# CL_meter.net
KiCad netlist of a schematic drawn in Altium Designer
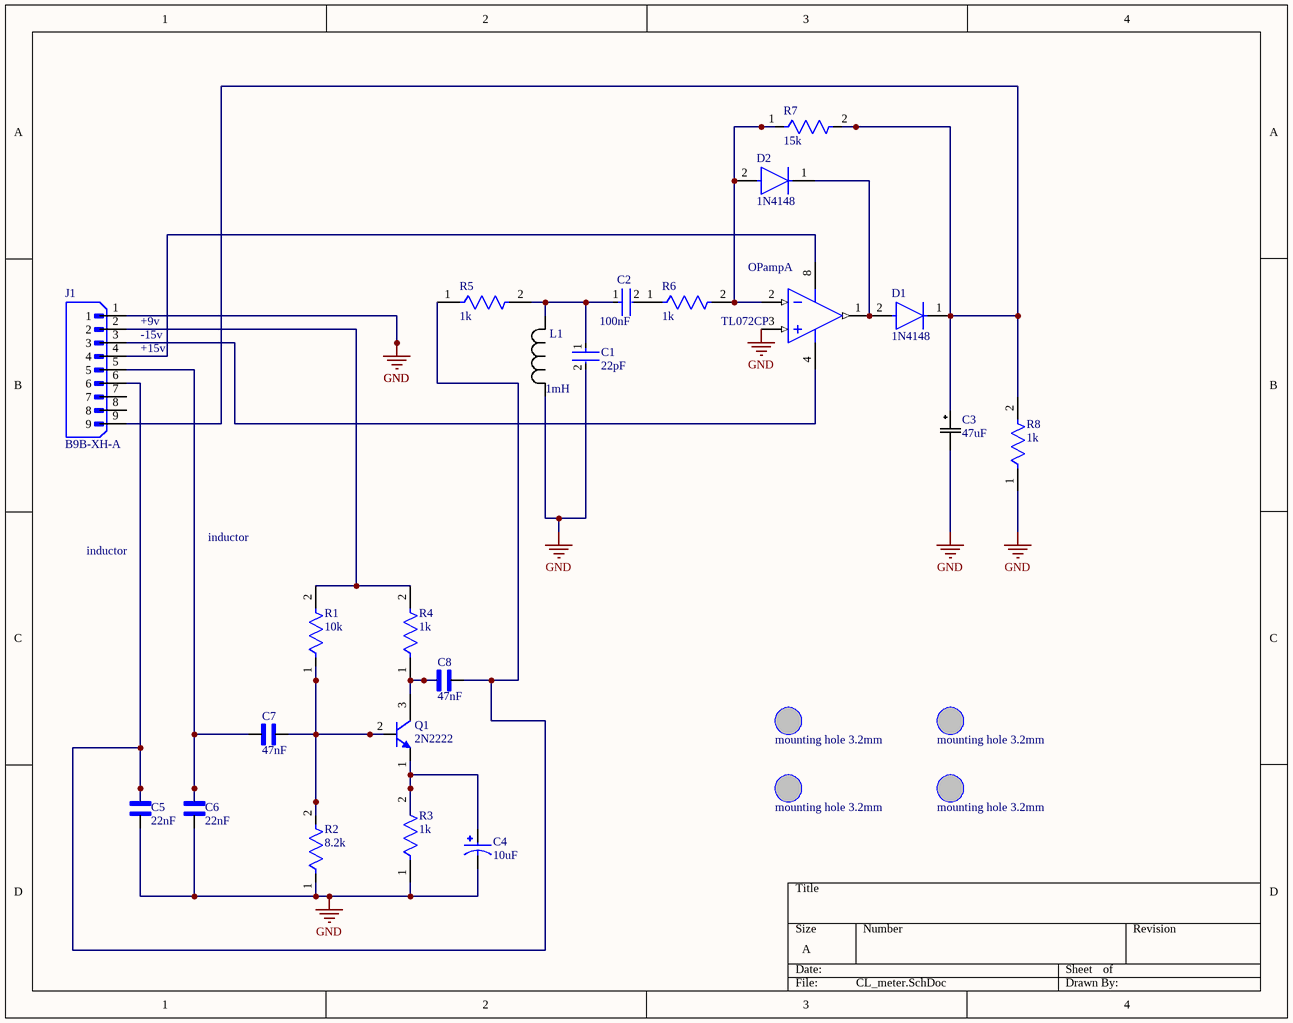
[diagram p0: CL_meter.SchDoc]

(export (version "E")
  (design (tool "Eeschema 10.0.6"))
  (components
    (comp (ref "C1")
      (value "22pF")
      (footprint "FP-DE2_D8_T5_F7_5_d0_6-0-MFG")
      (description "DE21XKY220JN3AM02F Cap Ceramic Disc 22pF 250VAC 5% Thru-Hole Ammo Pack")
      (fields (field (name "TOLERANCE") "5%"))
      (libsource (lib "Altium Content Vault") (part "2f572a3ab75e460155c5317ce189eff"))
    )
    (comp (ref "C2")
      (value "100nF")
      (footprint "FP-K15H5-MFG")
      (description "CAP CER 0.1UF 50V X7R RADIAL")
      (fields (field (name "TOLERANCE") "10%") (field (name "VOLTAGE") "50V"))
      (libsource (lib "Altium Content Vault") (part "02cd4be3c70576c341d710602a673aa"))
    )
    (comp (ref "C3")
      (value "47uF")
      (footprint "3")
      (description "No Description Available")
      (libsource (lib "Schlib1") (part "UVK2A470MPD1TD"))
    )
    (comp (ref "C4")
      (value "10uF")
      (footprint "10uF")
      (description "Cap Aluminum Lytic 10uF 25V 20% (4 X 7mm) Radial 5mm 28mA 1000h 85Â°C Ammo Pack")
      (fields (field (name "MP") "ECEA1EKA100B") (field (name "MF") "Panasonic"))
      (libsource (lib "Schlib1") (part "10uF"))
    )
    (comp (ref "C5")
      (value "22nF")
      (footprint "CAPRR254W54L381T254H466")
      (fields (field (name "MF") "KEMET") (field (name "MP") "C315C223K5R5TA"))
      (libsource (lib "Schlib1") (part "C315C223K5R5TA"))
    )
    (comp (ref "C6")
      (value "22nF")
      (footprint "CAPRR254W54L381T254H466")
      (fields (field (name "MF") "KEMET") (field (name "MP") "C315C223K5R5TA"))
      (libsource (lib "Schlib1") (part "C315C223K5R5TA"))
    )
    (comp (ref "C7")
      (value "47nF")
      (footprint "CAPRR254W54L381T254H466")
      (fields (field (name "MF") "KEMET") (field (name "MP") "C315C473M5U5TA"))
      (libsource (lib "Schlib1") (part "C315C473M5U5TA"))
    )
    (comp (ref "C8")
      (value "47nF")
      (footprint "CAPRR254W54L381T254H466")
      (fields (field (name "MF") "KEMET") (field (name "MP") "C315C473M5U5TA"))
      (libsource (lib "Schlib1") (part "C315C473M5U5TA"))
    )
    (comp (ref "D1")
      (value "1N4148")
      (footprint "FP-017AG-MFG")
      (description "DIODE GEN PURP 100V 200MA DO35")
      (fields (field (name "VOLTAGE") "100V"))
      (libsource (lib "Altium Content Vault") (part "d7152d700b627762746794eb795d46e"))
    )
    (comp (ref "D2")
      (value "1N4148")
      (footprint "FP-017AG-MFG")
      (description "DIODE GEN PURP 100V 200MA DO35")
      (fields (field (name "VOLTAGE") "100V"))
      (libsource (lib "Altium Content Vault") (part "d7152d700b627762746794eb795d46e"))
    )
    (comp (ref "J1")
      (value "B9B-XH-A")
      (footprint "JST_B9B-XH-A")
      (fields (field (name "MF") "{'manufacturer': u'JST Sales America Inc.'}"))
      (libsource (lib "Schlib1") (part "B9B-XH-A"))
    )
    (comp (ref "L1")
      (value "1mH")
      (footprint "IND_BOURNS_RLB9012")
      (description "No Description Available")
      (libsource (lib "Schlib1") (part "RLB9012-102KL"))
    )
    (comp (ref "OPamp")
      (value "TL072CP")
      (footprint "P0008A")
      (fields (field (name "MANUFACTURER") "Texas Instruments"))
      (libsource (lib "Altium Content Vault") (part "TI-AMP-D6-2-8_D"))
    )
    (comp (ref "Q1")
      (value "2N2222")
      (footprint "MLTC-TO-18-3")
      (description "Low Power Bipolar NPN Transistor, 30 V, -65 to 200 degC, 3-Pin TO-18, RoHS, Bulk")
      (fields (field (name "MANUFACTURER") "Multicomp"))
      (libsource (lib "Altium Content Vault") (part "BJT-NPN-EBC-3"))
    )
    (comp (ref "R1")
      (value "10k")
      (footprint "FP-MRS25-MFG")
      (fields (field (name "TOLERANCE") "1%"))
      (libsource (lib "Altium Content Vault") (part "1029c3af85768c4190bb7ad29bc67b5"))
    )
    (comp (ref "R2")
      (value "8.2k")
      (footprint "FP-MRS25-MFG")
      (fields (field (name "TOLERANCE") "1%"))
      (libsource (lib "Altium Content Vault") (part "1029c3af85768c4190bb7ad29bc67b5"))
    )
    (comp (ref "R3")
      (value "1k")
      (footprint "FP-MRS25-MFG")
      (fields (field (name "TOLERANCE") "1%"))
      (libsource (lib "Altium Content Vault") (part "1029c3af85768c4190bb7ad29bc67b5"))
    )
    (comp (ref "R4")
      (value "1k")
      (footprint "FP-MRS25-MFG")
      (fields (field (name "TOLERANCE") "1%"))
      (libsource (lib "Altium Content Vault") (part "1029c3af85768c4190bb7ad29bc67b5"))
    )
    (comp (ref "R5")
      (value "1k")
      (footprint "FP-MRS25-MFG")
      (fields (field (name "TOLERANCE") "1%"))
      (libsource (lib "Altium Content Vault") (part "1029c3af85768c4190bb7ad29bc67b5"))
    )
    (comp (ref "R6")
      (value "1k")
      (footprint "FP-MRS25-MFG")
      (fields (field (name "TOLERANCE") "1%"))
      (libsource (lib "Altium Content Vault") (part "1029c3af85768c4190bb7ad29bc67b5"))
    )
    (comp (ref "R7")
      (value "15k")
      (footprint "FP-MRS25-MFG")
      (fields (field (name "TOLERANCE") "1%"))
      (libsource (lib "Altium Content Vault") (part "1029c3af85768c4190bb7ad29bc67b5"))
    )
    (comp (ref "R8")
      (value "1k")
      (footprint "FP-MRS25-MFG")
      (fields (field (name "TOLERANCE") "1%"))
      (libsource (lib "Altium Content Vault") (part "1029c3af85768c4190bb7ad29bc67b5"))
    )
  )
  (nets
    (net (code "1") (name "GND") (class "Default")
      (node (ref "C1") (pin "2") (pinfunction "2_2") (pintype "passive"))
      (node (ref "C3") (pin "2") (pinfunction "2_2") (pintype "passive"))
      (node (ref "C4") (pin "N") (pinfunction "N_N") (pintype "passive"))
      (node (ref "C5") (pin "1") (pinfunction "1_1") (pintype "passive"))
      (node (ref "C6") (pin "1") (pinfunction "1_1") (pintype "passive"))
      (node (ref "J1") (pin "1") (pinfunction "1_1") (pintype "passive"))
      (node (ref "L1") (pin "2") (pinfunction "2_2") (pintype "passive"))
      (node (ref "OPamp") (pin "3") (pinfunction "IN1+_3") (pintype "input"))
      (node (ref "R2") (pin "1") (pinfunction "1_1") (pintype "passive"))
      (node (ref "R3") (pin "1") (pinfunction "1_1") (pintype "passive"))
      (node (ref "R8") (pin "1") (pinfunction "1_1") (pintype "passive"))
    )
    (net (code "2") (name "Net-(C1-Pad1)") (class "Default")
      (node (ref "C1") (pin "1") (pinfunction "1_1") (pintype "passive"))
      (node (ref "C2") (pin "1") (pinfunction "1_1") (pintype "passive"))
      (node (ref "L1") (pin "1") (pinfunction "1_1") (pintype "passive"))
      (node (ref "R5") (pin "2") (pinfunction "2_2") (pintype "passive"))
    )
    (net (code "3") (name "Net-(C2-Pad2)") (class "Default")
      (node (ref "C2") (pin "2") (pinfunction "2_2") (pintype "passive"))
      (node (ref "R6") (pin "1") (pinfunction "1_1") (pintype "passive"))
    )
    (net (code "4") (name "Net-(C5-Pad2)") (class "Default")
      (node (ref "C5") (pin "2") (pinfunction "2_2") (pintype "passive"))
      (node (ref "C8") (pin "2") (pinfunction "2_2") (pintype "passive"))
      (node (ref "J1") (pin "6") (pinfunction "6_6") (pintype "passive"))
      (node (ref "R5") (pin "1") (pinfunction "1_1") (pintype "passive"))
    )
    (net (code "5") (name "Net-(C6-Pad2)") (class "Default")
      (node (ref "C6") (pin "2") (pinfunction "2_2") (pintype "passive"))
      (node (ref "C7") (pin "1") (pinfunction "1_1") (pintype "passive"))
      (node (ref "J1") (pin "5") (pinfunction "5_5") (pintype "passive"))
    )
    (net (code "6") (name "Net-(D1-A)") (class "Default")
      (node (ref "D1") (pin "2") (pinfunction "A_2") (pintype "passive"))
      (node (ref "D2") (pin "1") (pinfunction "C_1") (pintype "passive"))
      (node (ref "OPamp") (pin "1") (pinfunction "OUT1_1") (pintype "output"))
    )
    (net (code "7") (name "Net-(D1-C)") (class "Default")
      (node (ref "C3") (pin "1") (pinfunction "1_1") (pintype "passive"))
      (node (ref "D1") (pin "1") (pinfunction "C_1") (pintype "passive"))
      (node (ref "J1") (pin "9") (pinfunction "9_9") (pintype "passive"))
      (node (ref "R7") (pin "2") (pinfunction "2_2") (pintype "passive"))
      (node (ref "R8") (pin "2") (pinfunction "2_2") (pintype "passive"))
    )
    (net (code "8") (name "Net-(D2-A)") (class "Default")
      (node (ref "D2") (pin "2") (pinfunction "A_2") (pintype "passive"))
      (node (ref "OPamp") (pin "2") (pinfunction "IN1-_2") (pintype "input"))
      (node (ref "R6") (pin "2") (pinfunction "2_2") (pintype "passive"))
      (node (ref "R7") (pin "1") (pinfunction "1_1") (pintype "passive"))
    )
    (net (code "9") (name "Net-(J1-Pad2)") (class "Default")
      (node (ref "J1") (pin "2") (pinfunction "2_2") (pintype "passive"))
      (node (ref "R1") (pin "2") (pinfunction "2_2") (pintype "passive"))
      (node (ref "R4") (pin "2") (pinfunction "2_2") (pintype "passive"))
    )
    (net (code "10") (name "Net-(OPampA-VCC+)") (class "Default")
      (node (ref "J1") (pin "4") (pinfunction "4_4") (pintype "passive"))
      (node (ref "OPamp") (pin "8") (pinfunction "VCC+_8") (pintype "power_in"))
    )
    (net (code "11") (name "Net-(OPampA-VCC-)") (class "Default")
      (node (ref "J1") (pin "3") (pinfunction "3_3") (pintype "passive"))
      (node (ref "OPamp") (pin "4") (pinfunction "VCC-_4") (pintype "power_in"))
    )
    (net (code "12") (name "Net-(Q1-B)") (class "Default")
      (node (ref "C7") (pin "2") (pinfunction "2_2") (pintype "passive"))
      (node (ref "Q1") (pin "2") (pinfunction "B_2") (pintype "passive"))
      (node (ref "R1") (pin "1") (pinfunction "1_1") (pintype "passive"))
      (node (ref "R2") (pin "2") (pinfunction "2_2") (pintype "passive"))
    )
    (net (code "13") (name "Net-(Q1-C)") (class "Default")
      (node (ref "C8") (pin "1") (pinfunction "1_1") (pintype "passive"))
      (node (ref "Q1") (pin "3") (pinfunction "C_3") (pintype "passive"))
      (node (ref "R4") (pin "1") (pinfunction "1_1") (pintype "passive"))
    )
    (net (code "14") (name "Net-(Q1-E)") (class "Default")
      (node (ref "C4") (pin "P") (pinfunction "P_P") (pintype "passive"))
      (node (ref "Q1") (pin "1") (pinfunction "E_1") (pintype "passive"))
      (node (ref "R3") (pin "2") (pinfunction "2_2") (pintype "passive"))
    )
    (net (code "15") (name "unconnected-(J1-Pad7)") (class "Default")
      (node (ref "J1") (pin "7") (pinfunction "7_7") (pintype "passive"))
    )
    (net (code "16") (name "unconnected-(J1-Pad8)") (class "Default")
      (node (ref "J1") (pin "8") (pinfunction "8_8") (pintype "passive"))
    )
  )
)
